# motor_control.net
KiCad netlist of a schematic drawn in Altium Designer
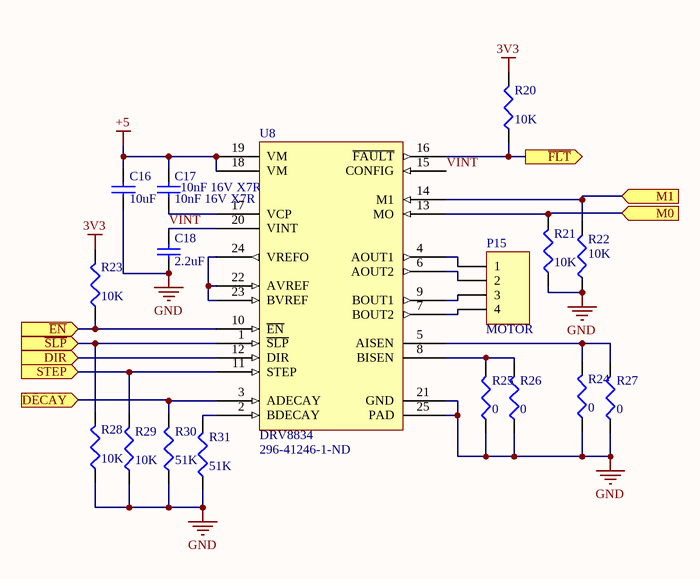
[diagram p0: motor_control.SchDoc]

(export (version "E")
  (design (tool "Eeschema 10.0.6"))
  (components
    (comp (ref "C16")
      (value "10uF")
      (footprint "1608[0603]")
      (description "Capacitor (Semiconductor SIM Model)")
      (fields (field (name "PUBLISHER") "Altium Limited"))
      (libsource (lib "Miscellaneous Devices") (part "Cap Semi"))
    )
    (comp (ref "C17")
      (value "10nF 16V X7R")
      (footprint "1608[0603]")
      (description "Capacitor (Semiconductor SIM Model)")
      (fields (field (name "ALTIUM_VALUE") "10nF 16V X7R") (field (name "PUBLISHER") "Altium Limited"))
      (libsource (lib "Miscellaneous Devices") (part "Cap Semi"))
    )
    (comp (ref "C18")
      (value "2.2uF")
      (footprint "1608[0603]")
      (description "Capacitor (Semiconductor SIM Model)")
      (fields (field (name "PUBLISHER") "Altium Limited"))
      (libsource (lib "Miscellaneous Devices") (part "Cap Semi"))
    )
    (comp (ref "P15")
      (value "MOTOR")
      (footprint "DF14-4P-1.25H(55)")
      (description "Header, 4-Pin")
      (fields (field (name "PUBLISHER") "Altium Limited"))
      (libsource (lib "Miscellaneous Connectors") (part "Header 4"))
    )
    (comp (ref "R20")
      (value "10K")
      (footprint "J1-0603")
      (description "Resistor")
      (fields (field (name "PUBLISHER") "Altium Limited"))
      (libsource (lib "Miscellaneous Devices") (part "Res3"))
    )
    (comp (ref "R21")
      (value "10K")
      (footprint "J1-0603")
      (description "Resistor")
      (fields (field (name "PUBLISHER") "Altium Limited"))
      (libsource (lib "Miscellaneous Devices") (part "Res3"))
    )
    (comp (ref "R22")
      (value "10K")
      (footprint "J1-0603")
      (description "Resistor")
      (fields (field (name "PUBLISHER") "Altium Limited"))
      (libsource (lib "Miscellaneous Devices") (part "Res3"))
    )
    (comp (ref "R23")
      (value "10K")
      (footprint "J1-0603")
      (description "Resistor")
      (fields (field (name "PUBLISHER") "Altium Limited"))
      (libsource (lib "Miscellaneous Devices") (part "Res3"))
    )
    (comp (ref "R24")
      (value "0")
      (footprint "J1-0603")
      (description "Resistor")
      (fields (field (name "PUBLISHER") "Altium Limited"))
      (libsource (lib "Miscellaneous Devices") (part "Res3"))
    )
    (comp (ref "R25")
      (value "0")
      (footprint "J1-0603")
      (description "Resistor")
      (fields (field (name "PUBLISHER") "Altium Limited"))
      (libsource (lib "Miscellaneous Devices") (part "Res3"))
    )
    (comp (ref "R26")
      (value "0")
      (footprint "J1-0603")
      (description "Resistor")
      (fields (field (name "PUBLISHER") "Altium Limited"))
      (libsource (lib "Miscellaneous Devices") (part "Res3"))
    )
    (comp (ref "R27")
      (value "0")
      (footprint "J1-0603")
      (description "Resistor")
      (fields (field (name "PUBLISHER") "Altium Limited"))
      (libsource (lib "Miscellaneous Devices") (part "Res3"))
    )
    (comp (ref "R28")
      (value "10K")
      (footprint "J1-0603")
      (description "Resistor")
      (fields (field (name "PUBLISHER") "Altium Limited"))
      (libsource (lib "Miscellaneous Devices") (part "Res3"))
    )
    (comp (ref "R29")
      (value "10K")
      (footprint "J1-0603")
      (description "Resistor")
      (fields (field (name "PUBLISHER") "Altium Limited"))
      (libsource (lib "Miscellaneous Devices") (part "Res3"))
    )
    (comp (ref "R30")
      (value "51K")
      (footprint "J1-0603")
      (description "Resistor")
      (fields (field (name "PUBLISHER") "Altium Limited"))
      (libsource (lib "Miscellaneous Devices") (part "Res3"))
    )
    (comp (ref "R31")
      (value "51K")
      (footprint "J1-0603")
      (description "Resistor")
      (fields (field (name "PUBLISHER") "Altium Limited"))
      (libsource (lib "Miscellaneous Devices") (part "Res3"))
    )
    (comp (ref "U8")
      (value "DRV8834")
      (footprint "SOP65P640X120-25N")
      (description "Dual-bridge stepper or dc motor driver. 1.5A per coil with 2.5-10.8 V load supply.")
      (fields (field (name "SUPPLIER PART NUMBER 1") "296-41246-1-ND"))
      (libsource (lib "PAY") (part "DRV8834"))
    )
  )
  (nets
    (net (code "1") (name "+5") (class "Default")
      (node (ref "C16") (pin "2") (pinfunction "2_2") (pintype "passive"))
      (node (ref "C17") (pin "2") (pinfunction "2_2") (pintype "passive"))
      (node (ref "U8") (pin "18") (pinfunction "VM_18") (pintype "power_in"))
      (node (ref "U8") (pin "19") (pinfunction "VM_19") (pintype "power_in"))
    )
    (net (code "2") (name "/DECAY") (class "Default")
      (node (ref "R30") (pin "2") (pinfunction "2_2") (pintype "passive"))
      (node (ref "U8") (pin "3") (pinfunction "ADECAY_3") (pintype "input"))
    )
    (net (code "3") (name "/DIR") (class "Default")
      (node (ref "U8") (pin "12") (pinfunction "DIR_12") (pintype "input"))
    )
    (net (code "4") (name "/M0") (class "Default")
      (node (ref "R21") (pin "2") (pinfunction "2_2") (pintype "passive"))
      (node (ref "U8") (pin "13") (pinfunction "MO_13") (pintype "input"))
    )
    (net (code "5") (name "/M1") (class "Default")
      (node (ref "R22") (pin "2") (pinfunction "2_2") (pintype "passive"))
      (node (ref "U8") (pin "14") (pinfunction "M1_14") (pintype "input"))
    )
    (net (code "6") (name "/STEP") (class "Default")
      (node (ref "R29") (pin "2") (pinfunction "2_2") (pintype "passive"))
      (node (ref "U8") (pin "11") (pinfunction "STEP_11") (pintype "input"))
    )
    (net (code "7") (name "/VINT") (class "Default")
      (node (ref "C18") (pin "2") (pinfunction "2_2") (pintype "passive"))
      (node (ref "U8") (pin "15") (pinfunction "CONFIG_15") (pintype "input"))
      (node (ref "U8") (pin "20") (pinfunction "VINT_20") (pintype "power_in"))
    )
    (net (code "8") (name "/~{EN}") (class "Default")
      (node (ref "R23") (pin "1") (pinfunction "1_1") (pintype "passive"))
      (node (ref "U8") (pin "10") (pinfunction "~{EN}_10") (pintype "input"))
    )
    (net (code "9") (name "/~{FLT}") (class "Default")
      (node (ref "R20") (pin "1") (pinfunction "1_1") (pintype "passive"))
      (node (ref "U8") (pin "16") (pinfunction "~{FAULT}_16") (pintype "output"))
    )
    (net (code "10") (name "/~{SLP}") (class "Default")
      (node (ref "R28") (pin "2") (pinfunction "2_2") (pintype "passive"))
      (node (ref "U8") (pin "1") (pinfunction "~{SLP}_1") (pintype "input"))
    )
    (net (code "11") (name "3V3") (class "Default")
      (node (ref "R20") (pin "2") (pinfunction "2_2") (pintype "passive"))
      (node (ref "R23") (pin "2") (pinfunction "2_2") (pintype "passive"))
    )
    (net (code "12") (name "GND") (class "Default")
      (node (ref "C16") (pin "1") (pinfunction "1_1") (pintype "passive"))
      (node (ref "C18") (pin "1") (pinfunction "1_1") (pintype "passive"))
      (node (ref "R21") (pin "1") (pinfunction "1_1") (pintype "passive"))
      (node (ref "R22") (pin "1") (pinfunction "1_1") (pintype "passive"))
      (node (ref "R24") (pin "1") (pinfunction "1_1") (pintype "passive"))
      (node (ref "R25") (pin "1") (pinfunction "1_1") (pintype "passive"))
      (node (ref "R26") (pin "1") (pinfunction "1_1") (pintype "passive"))
      (node (ref "R27") (pin "1") (pinfunction "1_1") (pintype "passive"))
      (node (ref "R28") (pin "1") (pinfunction "1_1") (pintype "passive"))
      (node (ref "R29") (pin "1") (pinfunction "1_1") (pintype "passive"))
      (node (ref "R30") (pin "1") (pinfunction "1_1") (pintype "passive"))
      (node (ref "R31") (pin "1") (pinfunction "1_1") (pintype "passive"))
      (node (ref "U8") (pin "21") (pinfunction "GND_21") (pintype "power_in"))
      (node (ref "U8") (pin "25") (pinfunction "PAD_25") (pintype "power_in"))
    )
    (net (code "13") (name "Net-(U8-AISEN)") (class "Default")
      (node (ref "R24") (pin "2") (pinfunction "2_2") (pintype "passive"))
      (node (ref "R27") (pin "2") (pinfunction "2_2") (pintype "passive"))
      (node (ref "U8") (pin "5") (pinfunction "AISEN_5") (pintype "passive"))
    )
    (net (code "14") (name "Net-(U8-AOUT1)") (class "Default")
      (node (ref "P15") (pin "1") (pinfunction "1_1") (pintype "passive"))
      (node (ref "U8") (pin "4") (pinfunction "AOUT1_4") (pintype "output"))
    )
    (net (code "15") (name "Net-(U8-AOUT2)") (class "Default")
      (node (ref "P15") (pin "2") (pinfunction "2_2") (pintype "passive"))
      (node (ref "U8") (pin "6") (pinfunction "AOUT2_6") (pintype "output"))
    )
    (net (code "16") (name "Net-(U8-AVREF)") (class "Default")
      (node (ref "U8") (pin "22") (pinfunction "AVREF_22") (pintype "input"))
      (node (ref "U8") (pin "23") (pinfunction "BVREF_23") (pintype "input"))
      (node (ref "U8") (pin "24") (pinfunction "VREFO_24") (pintype "output"))
    )
    (net (code "17") (name "Net-(U8-BDECAY)") (class "Default")
      (node (ref "R31") (pin "2") (pinfunction "2_2") (pintype "passive"))
      (node (ref "U8") (pin "2") (pinfunction "BDECAY_2") (pintype "input"))
    )
    (net (code "18") (name "Net-(U8-BISEN)") (class "Default")
      (node (ref "R25") (pin "2") (pinfunction "2_2") (pintype "passive"))
      (node (ref "R26") (pin "2") (pinfunction "2_2") (pintype "passive"))
      (node (ref "U8") (pin "8") (pinfunction "BISEN_8") (pintype "passive"))
    )
    (net (code "19") (name "Net-(U8-BOUT1)") (class "Default")
      (node (ref "P15") (pin "3") (pinfunction "3_3") (pintype "passive"))
      (node (ref "U8") (pin "9") (pinfunction "BOUT1_9") (pintype "output"))
    )
    (net (code "20") (name "Net-(U8-BOUT2)") (class "Default")
      (node (ref "P15") (pin "4") (pinfunction "4_4") (pintype "passive"))
      (node (ref "U8") (pin "7") (pinfunction "BOUT2_7") (pintype "output"))
    )
    (net (code "21") (name "Net-(U8-VCP)") (class "Default")
      (node (ref "C17") (pin "1") (pinfunction "1_1") (pintype "passive"))
      (node (ref "U8") (pin "17") (pinfunction "VCP_17") (pintype "power_in"))
    )
  )
)
